# PositionSensor.net
KiCad netlist of a schematic drawn in EAGLE
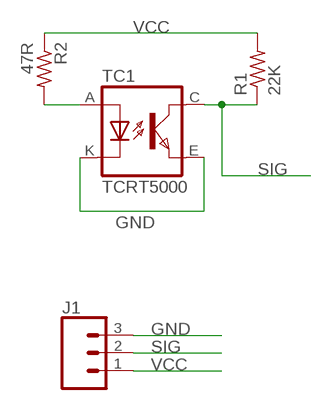
[diagram p0: schematic, sheet 1]

(export (version "E")
  (design (tool "Eeschema 10.0.6"))
  (components
    (comp (ref "J1")
      (value "CONN_03LONGPADS")
      (footprint "eagle-import:1X03_LONGPADS")
      (libsource (lib "eagle-import") (part "CONN_03LONGPADS"))
    )
    (comp (ref "R1")
      (value "22K")
      (footprint "eagle-import:0204_7")
      (libsource (lib "eagle-import") (part "R-US_0204/7"))
    )
    (comp (ref "R2")
      (value "47R")
      (footprint "eagle-import:0204_7")
      (libsource (lib "eagle-import") (part "R-US_0204/7"))
    )
    (comp (ref "TC1")
      (value "TCRT5000")
      (footprint "eagle-import:TCRT5000")
      (libsource (lib "eagle-import") (part "TCRT5000"))
    )
  )
  (nets
    (net (code "1") (name "/GND") (class "Default")
      (node (ref "J1") (pin "3") (pinfunction "3_3") (pintype "passive"))
      (node (ref "TC1") (pin "E") (pinfunction "EMITTER_E") (pintype "passive"))
      (node (ref "TC1") (pin "K") (pinfunction "CATHODE_K") (pintype "passive"))
    )
    (net (code "2") (name "/SIG") (class "Default")
      (node (ref "J1") (pin "2") (pinfunction "2_2") (pintype "passive"))
      (node (ref "R1") (pin "1") (pinfunction "1_1") (pintype "passive"))
      (node (ref "TC1") (pin "C") (pinfunction "COLLECTOR_C") (pintype "passive"))
    )
    (net (code "3") (name "/VCC") (class "Default")
      (node (ref "J1") (pin "1") (pinfunction "1_1") (pintype "passive"))
      (node (ref "R1") (pin "2") (pinfunction "2_2") (pintype "passive"))
      (node (ref "R2") (pin "1") (pinfunction "1_1") (pintype "passive"))
    )
    (net (code "4") (name "Net-(TC1-ANODE)") (class "Default")
      (node (ref "R2") (pin "2") (pinfunction "2_2") (pintype "passive"))
      (node (ref "TC1") (pin "A") (pinfunction "ANODE_A") (pintype "passive"))
    )
  )
)
